# Glasses.net
KiCad netlist of a schematic drawn in Altium Designer
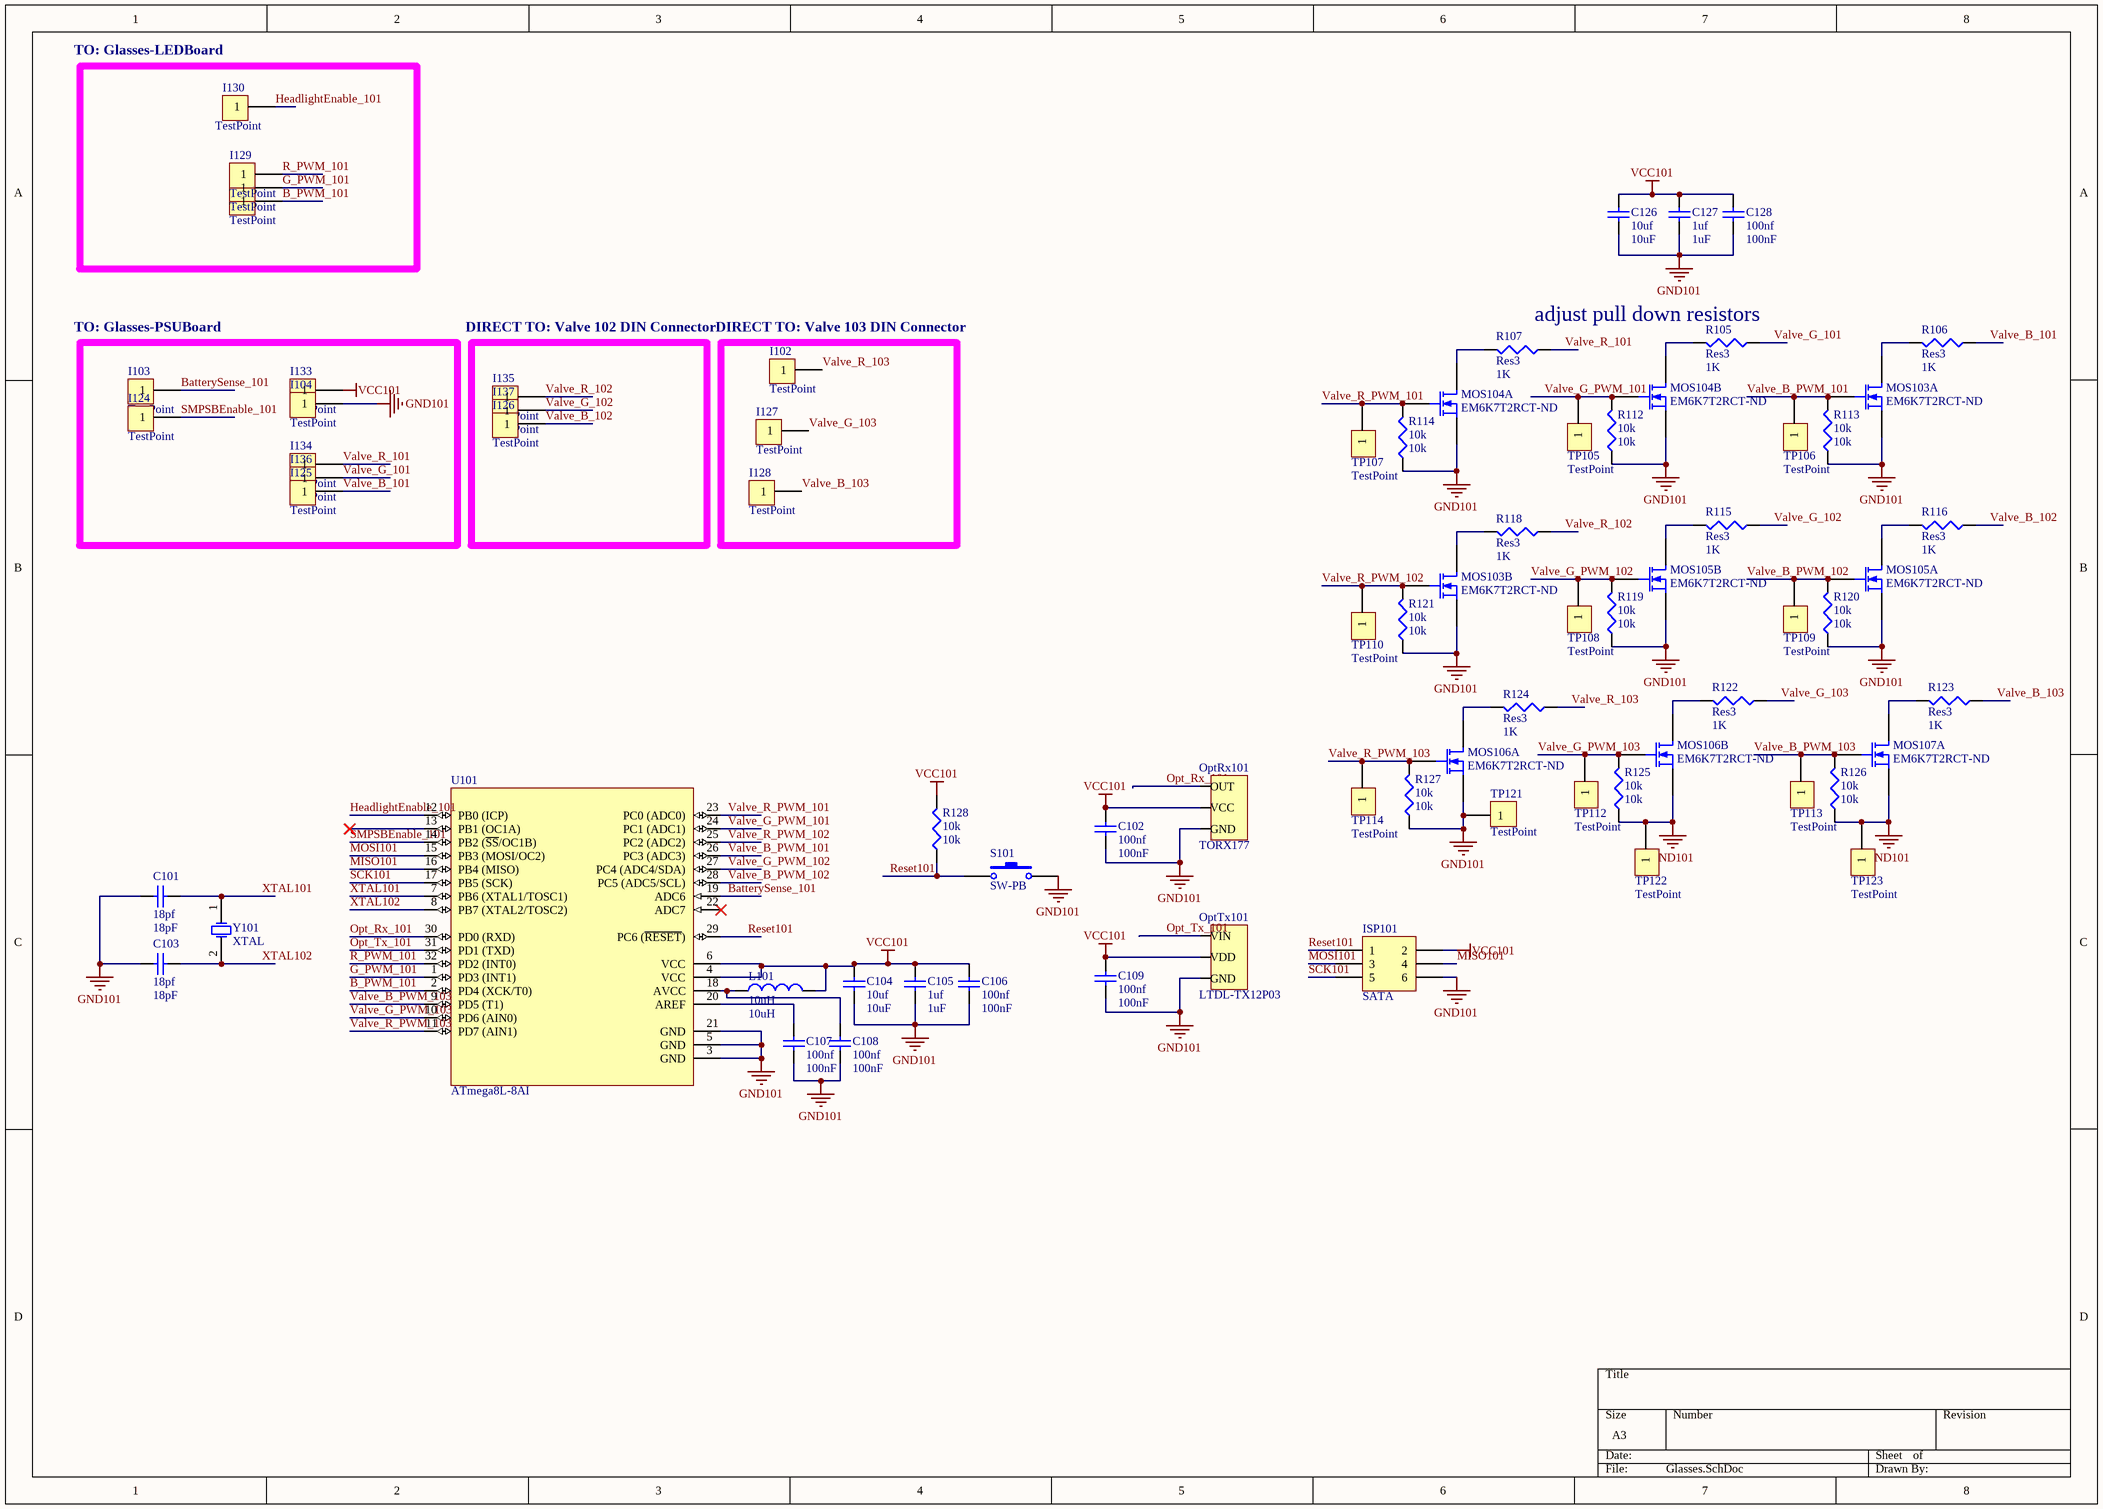
[diagram p0: Glasses.SchDoc]

(export (version "E")
  (design (tool "Eeschema 10.0.6"))
  (components
    (comp (ref "C101")
      (value "18pf")
      (footprint "0603")
      (description "Capacitor (Semiconductor SIM Model)")
      (fields (field (name "ALTIUM_VALUE") "18pF") (field (name "PUBLISHER") "Altium Limited"))
      (libsource (lib "Miscellaneous Devices") (part "Cap Semi"))
    )
    (comp (ref "C102")
      (value "100nf")
      (footprint "0603")
      (description "Capacitor (Semiconductor SIM Model)")
      (fields (field (name "ALTIUM_VALUE") "100nF") (field (name "PUBLISHER") "Altium Limited"))
      (libsource (lib "Miscellaneous Devices") (part "Cap Semi"))
    )
    (comp (ref "C103")
      (value "18pf")
      (footprint "0603")
      (description "Capacitor (Semiconductor SIM Model)")
      (fields (field (name "ALTIUM_VALUE") "18pF") (field (name "PUBLISHER") "Altium Limited"))
      (libsource (lib "Miscellaneous Devices") (part "Cap Semi"))
    )
    (comp (ref "C104")
      (value "10uf")
      (footprint "0805")
      (description "Capacitor (Semiconductor SIM Model)")
      (fields (field (name "ALTIUM_VALUE") "10uF") (field (name "PUBLISHER") "Altium Limited"))
      (libsource (lib "Miscellaneous Devices") (part "Cap Semi"))
    )
    (comp (ref "C105")
      (value "1uf")
      (footprint "0603")
      (description "Capacitor (Semiconductor SIM Model)")
      (fields (field (name "ALTIUM_VALUE") "1uF") (field (name "PUBLISHER") "Altium Limited"))
      (libsource (lib "Miscellaneous Devices") (part "Cap Semi"))
    )
    (comp (ref "C106")
      (value "100nf")
      (footprint "0603")
      (description "Capacitor (Semiconductor SIM Model)")
      (fields (field (name "ALTIUM_VALUE") "100nF") (field (name "PUBLISHER") "Altium Limited"))
      (libsource (lib "Miscellaneous Devices") (part "Cap Semi"))
    )
    (comp (ref "C107")
      (value "100nf")
      (footprint "0603")
      (description "Capacitor (Semiconductor SIM Model)")
      (fields (field (name "ALTIUM_VALUE") "100nF") (field (name "PUBLISHER") "Altium Limited"))
      (libsource (lib "Miscellaneous Devices") (part "Cap Semi"))
    )
    (comp (ref "C108")
      (value "100nf")
      (footprint "0603")
      (description "Capacitor (Semiconductor SIM Model)")
      (fields (field (name "ALTIUM_VALUE") "100nF") (field (name "PUBLISHER") "Altium Limited"))
      (libsource (lib "Miscellaneous Devices") (part "Cap Semi"))
    )
    (comp (ref "C109")
      (value "100nf")
      (footprint "0603")
      (description "Capacitor (Semiconductor SIM Model)")
      (fields (field (name "ALTIUM_VALUE") "100nF") (field (name "PUBLISHER") "Altium Limited"))
      (libsource (lib "Miscellaneous Devices") (part "Cap Semi"))
    )
    (comp (ref "C126")
      (value "10uf")
      (footprint "0805")
      (description "Capacitor (Semiconductor SIM Model)")
      (fields (field (name "ALTIUM_VALUE") "10uF") (field (name "PUBLISHER") "Altium Limited"))
      (libsource (lib "Miscellaneous Devices") (part "Cap Semi"))
    )
    (comp (ref "C127")
      (value "1uf")
      (footprint "0603")
      (description "Capacitor (Semiconductor SIM Model)")
      (fields (field (name "ALTIUM_VALUE") "1uF") (field (name "PUBLISHER") "Altium Limited"))
      (libsource (lib "Miscellaneous Devices") (part "Cap Semi"))
    )
    (comp (ref "C128")
      (value "100nf")
      (footprint "0603")
      (description "Capacitor (Semiconductor SIM Model)")
      (fields (field (name "ALTIUM_VALUE") "100nF") (field (name "PUBLISHER") "Altium Limited"))
      (libsource (lib "Miscellaneous Devices") (part "Cap Semi"))
    )
    (comp (ref "I102")
      (value "TestPoint")
      (footprint "TestPoint")
      (libsource (lib "Schlib1") (part "TestPoint"))
    )
    (comp (ref "I103")
      (value "TestPoint")
      (footprint "TestPoint")
      (libsource (lib "Schlib1") (part "TestPoint"))
    )
    (comp (ref "I104")
      (value "TestPoint")
      (footprint "TestPoint")
      (libsource (lib "Schlib1") (part "TestPoint"))
    )
    (comp (ref "I124")
      (value "TestPoint")
      (footprint "TestPoint")
      (libsource (lib "Schlib1") (part "TestPoint"))
    )
    (comp (ref "I125")
      (value "TestPoint")
      (footprint "TestPoint")
      (libsource (lib "Schlib1") (part "TestPoint"))
    )
    (comp (ref "I126")
      (value "TestPoint")
      (footprint "TestPoint")
      (libsource (lib "Schlib1") (part "TestPoint"))
    )
    (comp (ref "I127")
      (value "TestPoint")
      (footprint "TestPoint")
      (libsource (lib "Schlib1") (part "TestPoint"))
    )
    (comp (ref "I128")
      (value "TestPoint")
      (footprint "TestPoint")
      (libsource (lib "Schlib1") (part "TestPoint"))
    )
    (comp (ref "I129")
      (value "TestPoint")
      (footprint "TestPoint")
      (libsource (lib "Schlib1") (part "TestPoint"))
    )
    (comp (ref "I130")
      (value "TestPoint")
      (footprint "TestPoint")
      (libsource (lib "Schlib1") (part "TestPoint"))
    )
    (comp (ref "I131")
      (value "TestPoint")
      (footprint "TestPoint")
      (libsource (lib "Schlib1") (part "TestPoint"))
    )
    (comp (ref "I132")
      (value "TestPoint")
      (footprint "TestPoint")
      (libsource (lib "Schlib1") (part "TestPoint"))
    )
    (comp (ref "I133")
      (value "TestPoint")
      (footprint "TestPoint")
      (libsource (lib "Schlib1") (part "TestPoint"))
    )
    (comp (ref "I134")
      (value "TestPoint")
      (footprint "TestPoint")
      (libsource (lib "Schlib1") (part "TestPoint"))
    )
    (comp (ref "I135")
      (value "TestPoint")
      (footprint "TestPoint")
      (libsource (lib "Schlib1") (part "TestPoint"))
    )
    (comp (ref "I136")
      (value "TestPoint")
      (footprint "TestPoint")
      (libsource (lib "Schlib1") (part "TestPoint"))
    )
    (comp (ref "I137")
      (value "TestPoint")
      (footprint "TestPoint")
      (libsource (lib "Schlib1") (part "TestPoint"))
    )
    (comp (ref "ISP101")
      (value "SATA")
      (footprint "SATA")
      (description "Header, 3-Pin, Dual row")
      (fields (field (name "PUBLISHER") "Altium Limited"))
      (libsource (lib "Miscellaneous Connectors") (part "Header 3X2"))
    )
    (comp (ref "L101")
      (value "10uH")
      (footprint "0805")
      (description "Inductor")
      (fields (field (name "ALTIUM_VALUE") "10uH") (field (name "PUBLISHER") "Altium Limited"))
      (libsource (lib "Miscellaneous Devices") (part "Inductor"))
    )
    (comp (ref "MOS103")
      (value "EM6K7T2RCT-ND")
      (footprint "EM6K7T2R-EMT6")
      (libsource (lib "Schlib1") (part "EM6K7T2RCT-ND"))
    )
    (comp (ref "MOS104")
      (value "EM6K7T2RCT-ND")
      (footprint "EM6K7T2R-EMT6")
      (libsource (lib "Schlib1") (part "EM6K7T2RCT-ND"))
    )
    (comp (ref "MOS105")
      (value "EM6K7T2RCT-ND")
      (footprint "EM6K7T2R-EMT6")
      (libsource (lib "Schlib1") (part "EM6K7T2RCT-ND"))
    )
    (comp (ref "MOS106")
      (value "EM6K7T2RCT-ND")
      (footprint "EM6K7T2R-EMT6")
      (libsource (lib "Schlib1") (part "EM6K7T2RCT-ND"))
    )
    (comp (ref "MOS107")
      (value "EM6K7T2RCT-ND")
      (footprint "EM6K7T2R-EMT6")
      (libsource (lib "Schlib1") (part "EM6K7T2RCT-ND"))
    )
    (comp (ref "OptRx101")
      (value "TORX177")
      (footprint "Optical RX")
      (description "Optical receiver module")
      (libsource (lib "Schlib1") (part "TORX177"))
    )
    (comp (ref "OptTx101")
      (value "LTDL-TX12P03")
      (footprint "Optical TX")
      (description "Optical transmitter")
      (libsource (lib "Schlib1") (part "LTDL-TX12P03"))
    )
    (comp (ref "R105")
      (value "Res3")
      (footprint "0805")
      (description "Resistor")
      (fields (field (name "ALTIUM_VALUE") "1K") (field (name "PUBLISHER") "Altium Limited"))
      (libsource (lib "Miscellaneous Devices") (part "Res3"))
    )
    (comp (ref "R106")
      (value "Res3")
      (footprint "0805")
      (description "Resistor")
      (fields (field (name "ALTIUM_VALUE") "1K") (field (name "PUBLISHER") "Altium Limited"))
      (libsource (lib "Miscellaneous Devices") (part "Res3"))
    )
    (comp (ref "R107")
      (value "Res3")
      (footprint "0805")
      (description "Resistor")
      (fields (field (name "ALTIUM_VALUE") "1K") (field (name "PUBLISHER") "Altium Limited"))
      (libsource (lib "Miscellaneous Devices") (part "Res3"))
    )
    (comp (ref "R112")
      (value "10k")
      (footprint "0603")
      (description "Resistor")
      (fields (field (name "ALTIUM_VALUE") "10k") (field (name "PUBLISHER") "Altium Limited"))
      (libsource (lib "Miscellaneous Devices") (part "Res3"))
    )
    (comp (ref "R113")
      (value "10k")
      (footprint "0603")
      (description "Resistor")
      (fields (field (name "ALTIUM_VALUE") "10k") (field (name "PUBLISHER") "Altium Limited"))
      (libsource (lib "Miscellaneous Devices") (part "Res3"))
    )
    (comp (ref "R114")
      (value "10k")
      (footprint "0603")
      (description "Resistor")
      (fields (field (name "ALTIUM_VALUE") "10k") (field (name "PUBLISHER") "Altium Limited"))
      (libsource (lib "Miscellaneous Devices") (part "Res3"))
    )
    (comp (ref "R115")
      (value "Res3")
      (footprint "0805")
      (description "Resistor")
      (fields (field (name "ALTIUM_VALUE") "1K") (field (name "PUBLISHER") "Altium Limited"))
      (libsource (lib "Miscellaneous Devices") (part "Res3"))
    )
    (comp (ref "R116")
      (value "Res3")
      (footprint "0805")
      (description "Resistor")
      (fields (field (name "ALTIUM_VALUE") "1K") (field (name "PUBLISHER") "Altium Limited"))
      (libsource (lib "Miscellaneous Devices") (part "Res3"))
    )
    (comp (ref "R118")
      (value "Res3")
      (footprint "0805")
      (description "Resistor")
      (fields (field (name "ALTIUM_VALUE") "1K") (field (name "PUBLISHER") "Altium Limited"))
      (libsource (lib "Miscellaneous Devices") (part "Res3"))
    )
    (comp (ref "R119")
      (value "10k")
      (footprint "0603")
      (description "Resistor")
      (fields (field (name "ALTIUM_VALUE") "10k") (field (name "PUBLISHER") "Altium Limited"))
      (libsource (lib "Miscellaneous Devices") (part "Res3"))
    )
    (comp (ref "R120")
      (value "10k")
      (footprint "0603")
      (description "Resistor")
      (fields (field (name "ALTIUM_VALUE") "10k") (field (name "PUBLISHER") "Altium Limited"))
      (libsource (lib "Miscellaneous Devices") (part "Res3"))
    )
    (comp (ref "R121")
      (value "10k")
      (footprint "0603")
      (description "Resistor")
      (fields (field (name "ALTIUM_VALUE") "10k") (field (name "PUBLISHER") "Altium Limited"))
      (libsource (lib "Miscellaneous Devices") (part "Res3"))
    )
    (comp (ref "R122")
      (value "Res3")
      (footprint "0805")
      (description "Resistor")
      (fields (field (name "ALTIUM_VALUE") "1K") (field (name "PUBLISHER") "Altium Limited"))
      (libsource (lib "Miscellaneous Devices") (part "Res3"))
    )
    (comp (ref "R123")
      (value "Res3")
      (footprint "0805")
      (description "Resistor")
      (fields (field (name "ALTIUM_VALUE") "1K") (field (name "PUBLISHER") "Altium Limited"))
      (libsource (lib "Miscellaneous Devices") (part "Res3"))
    )
    (comp (ref "R124")
      (value "Res3")
      (footprint "0805")
      (description "Resistor")
      (fields (field (name "ALTIUM_VALUE") "1K") (field (name "PUBLISHER") "Altium Limited"))
      (libsource (lib "Miscellaneous Devices") (part "Res3"))
    )
    (comp (ref "R125")
      (value "10k")
      (footprint "0603")
      (description "Resistor")
      (fields (field (name "ALTIUM_VALUE") "10k") (field (name "PUBLISHER") "Altium Limited"))
      (libsource (lib "Miscellaneous Devices") (part "Res3"))
    )
    (comp (ref "R126")
      (value "10k")
      (footprint "0603")
      (description "Resistor")
      (fields (field (name "ALTIUM_VALUE") "10k") (field (name "PUBLISHER") "Altium Limited"))
      (libsource (lib "Miscellaneous Devices") (part "Res3"))
    )
    (comp (ref "R127")
      (value "10k")
      (footprint "0603")
      (description "Resistor")
      (fields (field (name "ALTIUM_VALUE") "10k") (field (name "PUBLISHER") "Altium Limited"))
      (libsource (lib "Miscellaneous Devices") (part "Res3"))
    )
    (comp (ref "R128")
      (value "10k")
      (footprint "0603")
      (description "Resistor")
      (fields (field (name "ALTIUM_VALUE") "10k") (field (name "PUBLISHER") "Altium Limited"))
      (libsource (lib "Miscellaneous Devices") (part "Res3"))
    )
    (comp (ref "S101")
      (value "SW-PB")
      (footprint "2 pin switch (surface mount)")
      (description "Switch")
      (fields (field (name "PUBLISHER") "Altium Limited"))
      (libsource (lib "Miscellaneous Devices") (part "SW-PB"))
    )
    (comp (ref "TP105") (value "TestPoint") (footprint "TestPoint") (libsource (lib "") (part "TestPoint_1")))
    (comp (ref "TP106") (value "TestPoint") (footprint "TestPoint") (libsource (lib "") (part "TestPoint_1")))
    (comp (ref "TP107") (value "TestPoint") (footprint "TestPoint") (libsource (lib "") (part "TestPoint_1")))
    (comp (ref "TP108") (value "TestPoint") (footprint "TestPoint") (libsource (lib "") (part "TestPoint_1")))
    (comp (ref "TP109") (value "TestPoint") (footprint "TestPoint") (libsource (lib "") (part "TestPoint_1")))
    (comp (ref "TP110") (value "TestPoint") (footprint "TestPoint") (libsource (lib "") (part "TestPoint_1")))
    (comp (ref "TP112") (value "TestPoint") (footprint "TestPoint") (libsource (lib "") (part "TestPoint_1")))
    (comp (ref "TP113") (value "TestPoint") (footprint "TestPoint") (libsource (lib "") (part "TestPoint_1")))
    (comp (ref "TP114") (value "TestPoint") (footprint "TestPoint") (libsource (lib "") (part "TestPoint_1")))
    (comp (ref "TP121") (value "TestPoint") (footprint "TestPoint") (libsource (lib "") (part "TestPoint_2")))
    (comp (ref "TP122") (value "TestPoint") (footprint "TestPoint") (libsource (lib "") (part "TestPoint_1")))
    (comp (ref "TP123") (value "TestPoint") (footprint "TestPoint") (libsource (lib "") (part "TestPoint_1")))
    (comp (ref "U101")
      (value "ATmega8L-8AI")
      (footprint "ATMega_GOOD")
      (description "8-Bit AVR Microcontroller with 8K Bytes of In-System Programmable Flash Memory")
      (fields (field (name "PUBLISHER") "Altium Limited"))
      (libsource (lib "Atmel Microcontroller 8-Bit AVR") (part "ATmega8L-8AI"))
    )
    (comp (ref "Y101")
      (value "XTAL")
      (footprint "ABLS-16MHz-B4-T")
      (description "Crystal Oscillator")
      (fields (field (name "PUBLISHER") "Altium Limited"))
      (libsource (lib "Miscellaneous Devices") (part "XTAL"))
    )
  )
  (nets
    (net (code "1") (name "/B_PWM_101") (class "Default")
      (node (ref "I132") (pin "1") (pinfunction "1_1") (pintype "passive"))
      (node (ref "U101") (pin "2") (pinfunction "PD4_(XCK/T0)_2") (pintype "bidirectional"))
    )
    (net (code "2") (name "/BatterySense_101") (class "Default")
      (node (ref "I103") (pin "1") (pinfunction "1_1") (pintype "passive"))
      (node (ref "U101") (pin "19") (pinfunction "ADC6_19") (pintype "input"))
    )
    (net (code "3") (name "/G_PWM_101") (class "Default")
      (node (ref "I131") (pin "1") (pinfunction "1_1") (pintype "passive"))
      (node (ref "U101") (pin "1") (pinfunction "PD3_(INT1)_1") (pintype "bidirectional"))
    )
    (net (code "4") (name "/HeadlightEnable_101") (class "Default")
      (node (ref "I130") (pin "1") (pinfunction "1_1") (pintype "passive"))
      (node (ref "U101") (pin "12") (pinfunction "PB0_(ICP)_12") (pintype "bidirectional"))
    )
    (net (code "5") (name "/MISO101") (class "Default")
      (node (ref "ISP101") (pin "4") (pinfunction "4_4") (pintype "passive"))
      (node (ref "U101") (pin "16") (pinfunction "PB4_(MISO)_16") (pintype "bidirectional"))
    )
    (net (code "6") (name "/MOSI101") (class "Default")
      (node (ref "ISP101") (pin "3") (pinfunction "3_3") (pintype "passive"))
      (node (ref "U101") (pin "15") (pinfunction "PB3_(MOSI/OC2)_15") (pintype "bidirectional"))
    )
    (net (code "7") (name "/Opt_Rx_101") (class "Default")
      (node (ref "OptRx101") (pin "1") (pinfunction "OUT_1") (pintype "passive"))
      (node (ref "U101") (pin "30") (pinfunction "PD0_(RXD)_30") (pintype "bidirectional"))
    )
    (net (code "8") (name "/Opt_Tx_101") (class "Default")
      (node (ref "OptTx101") (pin "1") (pinfunction "VIN_1") (pintype "passive"))
      (node (ref "U101") (pin "31") (pinfunction "PD1_(TXD)_31") (pintype "bidirectional"))
    )
    (net (code "9") (name "/R_PWM_101") (class "Default")
      (node (ref "I129") (pin "1") (pinfunction "1_1") (pintype "passive"))
      (node (ref "U101") (pin "32") (pinfunction "PD2_(INT0)_32") (pintype "bidirectional"))
    )
    (net (code "10") (name "/Reset101") (class "Default")
      (node (ref "ISP101") (pin "1") (pinfunction "1_1") (pintype "passive"))
      (node (ref "R128") (pin "1") (pinfunction "1_1") (pintype "passive"))
      (node (ref "S101") (pin "1") (pinfunction "1_1") (pintype "passive"))
      (node (ref "U101") (pin "29") (pinfunction "PC6_(~{RESET})_29") (pintype "bidirectional"))
    )
    (net (code "11") (name "/SCK101") (class "Default")
      (node (ref "ISP101") (pin "5") (pinfunction "5_5") (pintype "passive"))
      (node (ref "U101") (pin "17") (pinfunction "PB5_(SCK)_17") (pintype "bidirectional"))
    )
    (net (code "12") (name "/SMPSBEnable_101") (class "Default")
      (node (ref "I124") (pin "1") (pinfunction "1_1") (pintype "passive"))
      (node (ref "U101") (pin "14") (pinfunction "PB2_(~{SS}/OC1B)_14") (pintype "bidirectional"))
    )
    (net (code "13") (name "/Valve_B_101") (class "Default")
      (node (ref "I125") (pin "1") (pinfunction "1_1") (pintype "passive"))
      (node (ref "R106") (pin "1") (pinfunction "1_1") (pintype "passive"))
    )
    (net (code "14") (name "/Valve_B_102") (class "Default")
      (node (ref "I126") (pin "1") (pinfunction "1_1") (pintype "passive"))
      (node (ref "R116") (pin "1") (pinfunction "1_1") (pintype "passive"))
    )
    (net (code "15") (name "/Valve_B_103") (class "Default")
      (node (ref "I128") (pin "1") (pinfunction "1_1") (pintype "passive"))
      (node (ref "R123") (pin "1") (pinfunction "1_1") (pintype "passive"))
    )
    (net (code "16") (name "/Valve_B_PWM_101") (class "Default")
      (node (ref "MOS103") (pin "2") (pinfunction "G_2") (pintype "passive"))
      (node (ref "R113") (pin "2") (pinfunction "2_2") (pintype "passive"))
      (node (ref "TP106") (pin "1") (pinfunction "1_1") (pintype "passive"))
      (node (ref "U101") (pin "26") (pinfunction "PC3_(ADC3)_26") (pintype "bidirectional"))
    )
    (net (code "17") (name "/Valve_B_PWM_102") (class "Default")
      (node (ref "MOS105") (pin "2") (pinfunction "G_2") (pintype "passive"))
      (node (ref "R120") (pin "2") (pinfunction "2_2") (pintype "passive"))
      (node (ref "TP109") (pin "1") (pinfunction "1_1") (pintype "passive"))
      (node (ref "U101") (pin "28") (pinfunction "PC5_(ADC5/SCL)_28") (pintype "bidirectional"))
    )
    (net (code "18") (name "/Valve_B_PWM_103") (class "Default")
      (node (ref "MOS107") (pin "2") (pinfunction "G_2") (pintype "passive"))
      (node (ref "R126") (pin "2") (pinfunction "2_2") (pintype "passive"))
      (node (ref "TP113") (pin "1") (pinfunction "1_1") (pintype "passive"))
      (node (ref "U101") (pin "9") (pinfunction "PD5_(T1)_9") (pintype "bidirectional"))
    )
    (net (code "19") (name "/Valve_G_101") (class "Default")
      (node (ref "I136") (pin "1") (pinfunction "1_1") (pintype "passive"))
      (node (ref "R105") (pin "1") (pinfunction "1_1") (pintype "passive"))
    )
    (net (code "20") (name "/Valve_G_102") (class "Default")
      (node (ref "I137") (pin "1") (pinfunction "1_1") (pintype "passive"))
      (node (ref "R115") (pin "1") (pinfunction "1_1") (pintype "passive"))
    )
    (net (code "21") (name "/Valve_G_103") (class "Default")
      (node (ref "I127") (pin "1") (pinfunction "1_1") (pintype "passive"))
      (node (ref "R122") (pin "1") (pinfunction "1_1") (pintype "passive"))
    )
    (net (code "22") (name "/Valve_G_PWM_101") (class "Default")
      (node (ref "MOS104") (pin "5") (pinfunction "G_5") (pintype "passive"))
      (node (ref "R112") (pin "2") (pinfunction "2_2") (pintype "passive"))
      (node (ref "TP105") (pin "1") (pinfunction "1_1") (pintype "passive"))
      (node (ref "U101") (pin "24") (pinfunction "PC1_(ADC1)_24") (pintype "bidirectional"))
    )
    (net (code "23") (name "/Valve_G_PWM_102") (class "Default")
      (node (ref "MOS105") (pin "5") (pinfunction "G_5") (pintype "passive"))
      (node (ref "R119") (pin "2") (pinfunction "2_2") (pintype "passive"))
      (node (ref "TP108") (pin "1") (pinfunction "1_1") (pintype "passive"))
      (node (ref "U101") (pin "27") (pinfunction "PC4_(ADC4/SDA)_27") (pintype "bidirectional"))
    )
    (net (code "24") (name "/Valve_G_PWM_103") (class "Default")
      (node (ref "MOS106") (pin "5") (pinfunction "G_5") (pintype "passive"))
      (node (ref "R125") (pin "2") (pinfunction "2_2") (pintype "passive"))
      (node (ref "TP112") (pin "1") (pinfunction "1_1") (pintype "passive"))
      (node (ref "U101") (pin "10") (pinfunction "PD6_(AIN0)_10") (pintype "bidirectional"))
    )
    (net (code "25") (name "/Valve_R_101") (class "Default")
      (node (ref "I134") (pin "1") (pinfunction "1_1") (pintype "passive"))
      (node (ref "R107") (pin "1") (pinfunction "1_1") (pintype "passive"))
    )
    (net (code "26") (name "/Valve_R_102") (class "Default")
      (node (ref "I135") (pin "1") (pinfunction "1_1") (pintype "passive"))
      (node (ref "R118") (pin "1") (pinfunction "1_1") (pintype "passive"))
    )
    (net (code "27") (name "/Valve_R_103") (class "Default")
      (node (ref "I102") (pin "1") (pinfunction "1_1") (pintype "passive"))
      (node (ref "R124") (pin "1") (pinfunction "1_1") (pintype "passive"))
    )
    (net (code "28") (name "/Valve_R_PWM_101") (class "Default")
      (node (ref "MOS104") (pin "2") (pinfunction "G_2") (pintype "passive"))
      (node (ref "R114") (pin "2") (pinfunction "2_2") (pintype "passive"))
      (node (ref "TP107") (pin "1") (pinfunction "1_1") (pintype "passive"))
      (node (ref "U101") (pin "23") (pinfunction "PC0_(ADC0)_23") (pintype "bidirectional"))
    )
    (net (code "29") (name "/Valve_R_PWM_102") (class "Default")
      (node (ref "MOS103") (pin "5") (pinfunction "G_5") (pintype "passive"))
      (node (ref "R121") (pin "2") (pinfunction "2_2") (pintype "passive"))
      (node (ref "TP110") (pin "1") (pinfunction "1_1") (pintype "passive"))
      (node (ref "U101") (pin "25") (pinfunction "PC2_(ADC2)_25") (pintype "bidirectional"))
    )
    (net (code "30") (name "/Valve_R_PWM_103") (class "Default")
      (node (ref "MOS106") (pin "2") (pinfunction "G_2") (pintype "passive"))
      (node (ref "R127") (pin "2") (pinfunction "2_2") (pintype "passive"))
      (node (ref "TP114") (pin "1") (pinfunction "1_1") (pintype "passive"))
      (node (ref "U101") (pin "11") (pinfunction "PD7_(AIN1)_11") (pintype "bidirectional"))
    )
    (net (code "31") (name "/XTAL101") (class "Default")
      (node (ref "C101") (pin "2") (pinfunction "2_2") (pintype "passive"))
      (node (ref "U101") (pin "7") (pinfunction "PB6_(XTAL1/TOSC1)_7") (pintype "bidirectional"))
      (node (ref "Y101") (pin "1") (pinfunction "OSC1_1") (pintype "passive"))
    )
    (net (code "32") (name "/XTAL102") (class "Default")
      (node (ref "C103") (pin "2") (pinfunction "2_2") (pintype "passive"))
      (node (ref "U101") (pin "8") (pinfunction "PB7_(XTAL2/TOSC2)_8") (pintype "bidirectional"))
      (node (ref "Y101") (pin "2") (pinfunction "OSC2_2") (pintype "passive"))
    )
    (net (code "33") (name "GND101") (class "Default")
      (node (ref "C101") (pin "1") (pinfunction "1_1") (pintype "passive"))
      (node (ref "C102") (pin "1") (pinfunction "1_1") (pintype "passive"))
      (node (ref "C103") (pin "1") (pinfunction "1_1") (pintype "passive"))
      (node (ref "C104") (pin "1") (pinfunction "1_1") (pintype "passive"))
      (node (ref "C105") (pin "1") (pinfunction "1_1") (pintype "passive"))
      (node (ref "C106") (pin "1") (pinfunction "1_1") (pintype "passive"))
      (node (ref "C107") (pin "1") (pinfunction "1_1") (pintype "passive"))
      (node (ref "C108") (pin "1") (pinfunction "1_1") (pintype "passive"))
      (node (ref "C109") (pin "1") (pinfunction "1_1") (pintype "passive"))
      (node (ref "C126") (pin "1") (pinfunction "1_1") (pintype "passive"))
      (node (ref "C127") (pin "1") (pinfunction "1_1") (pintype "passive"))
      (node (ref "C128") (pin "1") (pinfunction "1_1") (pintype "passive"))
      (node (ref "I104") (pin "1") (pinfunction "1_1") (pintype "passive"))
      (node (ref "ISP101") (pin "6") (pinfunction "6_6") (pintype "passive"))
      (node (ref "MOS103") (pin "1") (pinfunction "S_1") (pintype "passive"))
      (node (ref "MOS103") (pin "4") (pinfunction "S_4") (pintype "passive"))
      (node (ref "MOS104") (pin "1") (pinfunction "S_1") (pintype "passive"))
      (node (ref "MOS104") (pin "4") (pinfunction "S_4") (pintype "passive"))
      (node (ref "MOS105") (pin "1") (pinfunction "S_1") (pintype "passive"))
      (node (ref "MOS105") (pin "4") (pinfunction "S_4") (pintype "passive"))
      (node (ref "MOS106") (pin "1") (pinfunction "S_1") (pintype "passive"))
      (node (ref "MOS106") (pin "4") (pinfunction "S_4") (pintype "passive"))
      (node (ref "MOS107") (pin "1") (pinfunction "S_1") (pintype "passive"))
      (node (ref "OptRx101") (pin "3") (pinfunction "GND_3") (pintype "passive"))
      (node (ref "OptTx101") (pin "3") (pinfunction "GND_3") (pintype "passive"))
      (node (ref "R112") (pin "1") (pinfunction "1_1") (pintype "passive"))
      (node (ref "R113") (pin "1") (pinfunction "1_1") (pintype "passive"))
      (node (ref "R114") (pin "1") (pinfunction "1_1") (pintype "passive"))
      (node (ref "R119") (pin "1") (pinfunction "1_1") (pintype "passive"))
      (node (ref "R120") (pin "1") (pinfunction "1_1") (pintype "passive"))
      (node (ref "R121") (pin "1") (pinfunction "1_1") (pintype "passive"))
      (node (ref "R125") (pin "1") (pinfunction "1_1") (pintype "passive"))
      (node (ref "R126") (pin "1") (pinfunction "1_1") (pintype "passive"))
      (node (ref "R127") (pin "1") (pinfunction "1_1") (pintype "passive"))
      (node (ref "S101") (pin "2") (pinfunction "2_2") (pintype "passive"))
      (node (ref "TP121") (pin "1") (pinfunction "1_1") (pintype "passive"))
      (node (ref "TP122") (pin "1") (pinfunction "1_1") (pintype "passive"))
      (node (ref "TP123") (pin "1") (pinfunction "1_1") (pintype "passive"))
      (node (ref "U101") (pin "21") (pinfunction "GND_21") (pintype "power_in"))
      (node (ref "U101") (pin "3") (pinfunction "GND_3") (pintype "power_in"))
      (node (ref "U101") (pin "5") (pinfunction "GND_5") (pintype "power_in"))
    )
    (net (code "34") (name "Net-(MOS103A-D)") (class "Default")
      (node (ref "MOS103") (pin "6") (pinfunction "D_6") (pintype "passive"))
      (node (ref "R106") (pin "2") (pinfunction "2_2") (pintype "passive"))
    )
    (net (code "35") (name "Net-(MOS103B-D)") (class "Default")
      (node (ref "MOS103") (pin "3") (pinfunction "D_3") (pintype "passive"))
      (node (ref "R118") (pin "2") (pinfunction "2_2") (pintype "passive"))
    )
    (net (code "36") (name "Net-(MOS104A-D)") (class "Default")
      (node (ref "MOS104") (pin "6") (pinfunction "D_6") (pintype "passive"))
      (node (ref "R107") (pin "2") (pinfunction "2_2") (pintype "passive"))
    )
    (net (code "37") (name "Net-(MOS104B-D)") (class "Default")
      (node (ref "MOS104") (pin "3") (pinfunction "D_3") (pintype "passive"))
      (node (ref "R105") (pin "2") (pinfunction "2_2") (pintype "passive"))
    )
    (net (code "38") (name "Net-(MOS105A-D)") (class "Default")
      (node (ref "MOS105") (pin "6") (pinfunction "D_6") (pintype "passive"))
      (node (ref "R116") (pin "2") (pinfunction "2_2") (pintype "passive"))
    )
    (net (code "39") (name "Net-(MOS105B-D)") (class "Default")
      (node (ref "MOS105") (pin "3") (pinfunction "D_3") (pintype "passive"))
      (node (ref "R115") (pin "2") (pinfunction "2_2") (pintype "passive"))
    )
    (net (code "40") (name "Net-(MOS106A-D)") (class "Default")
      (node (ref "MOS106") (pin "6") (pinfunction "D_6") (pintype "passive"))
      (node (ref "R124") (pin "2") (pinfunction "2_2") (pintype "passive"))
    )
    (net (code "41") (name "Net-(MOS106B-D)") (class "Default")
      (node (ref "MOS106") (pin "3") (pinfunction "D_3") (pintype "passive"))
      (node (ref "R122") (pin "2") (pinfunction "2_2") (pintype "passive"))
    )
    (net (code "42") (name "Net-(MOS107A-D)") (class "Default")
      (node (ref "MOS107") (pin "6") (pinfunction "D_6") (pintype "passive"))
      (node (ref "R123") (pin "2") (pinfunction "2_2") (pintype "passive"))
    )
    (net (code "43") (name "Net-(U101-AREF)") (class "Default")
      (node (ref "C107") (pin "2") (pinfunction "2_2") (pintype "passive"))
      (node (ref "U101") (pin "20") (pinfunction "AREF_20") (pintype "passive"))
    )
    (net (code "44") (name "Net-(U101-AVCC)") (class "Default")
      (node (ref "C108") (pin "2") (pinfunction "2_2") (pintype "passive"))
      (node (ref "L101") (pin "1") (pinfunction "1_1") (pintype "passive"))
      (node (ref "U101") (pin "18") (pinfunction "AVCC_18") (pintype "power_in"))
    )
    (net (code "45") (name "VCC101") (class "Default")
      (node (ref "C102") (pin "2") (pinfunction "2_2") (pintype "passive"))
      (node (ref "C104") (pin "2") (pinfunction "2_2") (pintype "passive"))
      (node (ref "C105") (pin "2") (pinfunction "2_2") (pintype "passive"))
      (node (ref "C106") (pin "2") (pinfunction "2_2") (pintype "passive"))
      (node (ref "C109") (pin "2") (pinfunction "2_2") (pintype "passive"))
      (node (ref "C126") (pin "2") (pinfunction "2_2") (pintype "passive"))
      (node (ref "C127") (pin "2") (pinfunction "2_2") (pintype "passive"))
      (node (ref "C128") (pin "2") (pinfunction "2_2") (pintype "passive"))
      (node (ref "I133") (pin "1") (pinfunction "1_1") (pintype "passive"))
      (node (ref "ISP101") (pin "2") (pinfunction "2_2") (pintype "passive"))
      (node (ref "L101") (pin "2") (pinfunction "2_2") (pintype "passive"))
      (node (ref "OptRx101") (pin "2") (pinfunction "VCC_2") (pintype "passive"))
      (node (ref "OptTx101") (pin "2") (pinfunction "VDD_2") (pintype "passive"))
      (node (ref "R128") (pin "2") (pinfunction "2_2") (pintype "passive"))
      (node (ref "U101") (pin "4") (pinfunction "VCC_4") (pintype "power_in"))
      (node (ref "U101") (pin "6") (pinfunction "VCC_6") (pintype "power_in"))
    )
    (net (code "46") (name "unconnected-(U101-ADC7-Pad22)") (class "Default")
      (node (ref "U101") (pin "22") (pinfunction "ADC7_22") (pintype "input+no_connect"))
    )
    (net (code "47") (name "unconnected-(U101-PB1_(OC1A)-Pad13)") (class "Default")
      (node (ref "U101") (pin "13") (pinfunction "PB1_(OC1A)_13") (pintype "bidirectional+no_connect"))
    )
  )
)
